# MPPT.net
KiCad netlist of a schematic drawn in Altium Designer
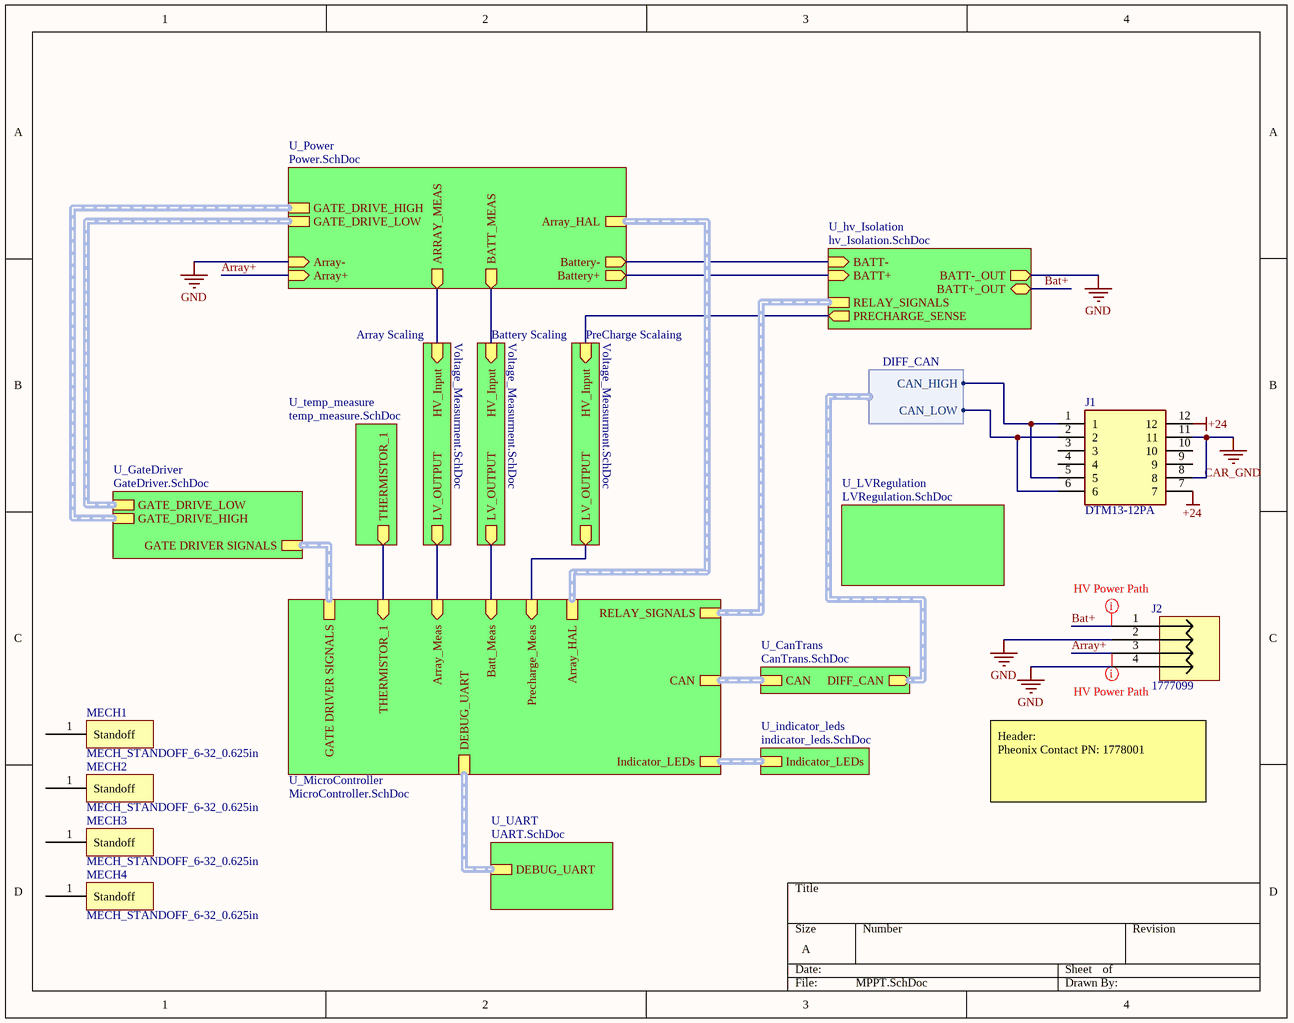
[diagram p0: MPPT.SchDoc]

(export (version "E")
  (design (tool "Eeschema 10.0.6"))
  (components
    (comp (ref "J1")
      (value "DTM13-12PA")
      (footprint "TE_DTM13-12PA")
      (libsource (lib "University of Minnesota - Solar Vehicle Project") (part "DTM13-12PA"))
    )
    (comp (ref "J2")
      (value "1777099")
      (footprint "FP-1777099-MFG")
      (description "Strip Terminal Block, 12A, 1 Row(s), 1 Deck(s)")
      (libsource (lib "") (part "Symbol_1"))
    )
    (comp (ref "MECH1")
      (value "MECH_STANDOFF_6-32_0.625in")
      (footprint "STANDOFF_6-32_0.625in")
      (description "Hex Standoff Threaded #6-32 Aluminum 0.625\" (15.88mm) 5/8\"")
      (libsource (lib "University of Minnesota - Solar Vehicle Project") (part "Symbol"))
    )
    (comp (ref "MECH2")
      (value "MECH_STANDOFF_6-32_0.625in")
      (footprint "STANDOFF_6-32_0.625in")
      (description "Hex Standoff Threaded #6-32 Aluminum 0.625\" (15.88mm) 5/8\"")
      (libsource (lib "University of Minnesota - Solar Vehicle Project") (part "Symbol"))
    )
    (comp (ref "MECH3")
      (value "MECH_STANDOFF_6-32_0.625in")
      (footprint "STANDOFF_6-32_0.625in")
      (description "Hex Standoff Threaded #6-32 Aluminum 0.625\" (15.88mm) 5/8\"")
      (libsource (lib "University of Minnesota - Solar Vehicle Project") (part "Symbol"))
    )
    (comp (ref "MECH4")
      (value "MECH_STANDOFF_6-32_0.625in")
      (footprint "STANDOFF_6-32_0.625in")
      (description "Hex Standoff Threaded #6-32 Aluminum 0.625\" (15.88mm) 5/8\"")
      (libsource (lib "University of Minnesota - Solar Vehicle Project") (part "Symbol"))
    )
  )
  (nets
    (net (code "2") (name "+24") (class "Default")
      (node (ref "J1") (pin "12") (pinfunction "12_12") (pintype "passive"))
      (node (ref "J1") (pin "7") (pinfunction "7_7") (pintype "passive"))
    )
    (net (code "4") (name "/Array+") (class "Default")
      (node (ref "J2") (pin "3") (pinfunction "3_3") (pintype "passive"))
    )
    (net (code "7") (name "/Bat+") (class "Default")
      (node (ref "J2") (pin "1") (pinfunction "1_1") (pintype "passive"))
    )
    (net (code "23") (name "CAR_GND") (class "Default")
      (node (ref "J1") (pin "11") (pinfunction "11_11") (pintype "passive"))
      (node (ref "J1") (pin "8") (pinfunction "8_8") (pintype "passive"))
    )
    (net (code "24") (name "GND") (class "Default")
      (node (ref "J2") (pin "2") (pinfunction "2_2") (pintype "passive"))
      (node (ref "J2") (pin "4") (pinfunction "4_4") (pintype "passive"))
    )
    (net (code "25") (name "Net-(J1-Pad1)") (class "Default")
      (node (ref "J1") (pin "1") (pinfunction "1_1") (pintype "passive"))
      (node (ref "J1") (pin "5") (pinfunction "5_5") (pintype "passive"))
    )
    (net (code "26") (name "Net-(J1-Pad2)") (class "Default")
      (node (ref "J1") (pin "2") (pinfunction "2_2") (pintype "passive"))
      (node (ref "J1") (pin "6") (pinfunction "6_6") (pintype "passive"))
    )
    (net (code "27") (name "unconnected-(J1-Pad3)") (class "Default")
      (node (ref "J1") (pin "3") (pinfunction "3_3") (pintype "passive"))
    )
    (net (code "28") (name "unconnected-(J1-Pad4)") (class "Default")
      (node (ref "J1") (pin "4") (pinfunction "4_4") (pintype "passive"))
    )
    (net (code "29") (name "unconnected-(J1-Pad9)") (class "Default")
      (node (ref "J1") (pin "9") (pinfunction "9_9") (pintype "passive"))
    )
    (net (code "30") (name "unconnected-(J1-Pad10)") (class "Default")
      (node (ref "J1") (pin "10") (pinfunction "10_10") (pintype "passive"))
    )
    (net (code "31") (name "unconnected-(MECH1-Standoff-Pad1)") (class "Default")
      (node (ref "MECH1") (pin "1") (pinfunction "Standoff_1") (pintype "passive"))
    )
    (net (code "32") (name "unconnected-(MECH2-Standoff-Pad1)") (class "Default")
      (node (ref "MECH2") (pin "1") (pinfunction "Standoff_1") (pintype "passive"))
    )
    (net (code "33") (name "unconnected-(MECH3-Standoff-Pad1)") (class "Default")
      (node (ref "MECH3") (pin "1") (pinfunction "Standoff_1") (pintype "passive"))
    )
    (net (code "34") (name "unconnected-(MECH4-Standoff-Pad1)") (class "Default")
      (node (ref "MECH4") (pin "1") (pinfunction "Standoff_1") (pintype "passive"))
    )
  )
)
